# untitled2.net
KiCad netlist of a schematic drawn in EAGLE
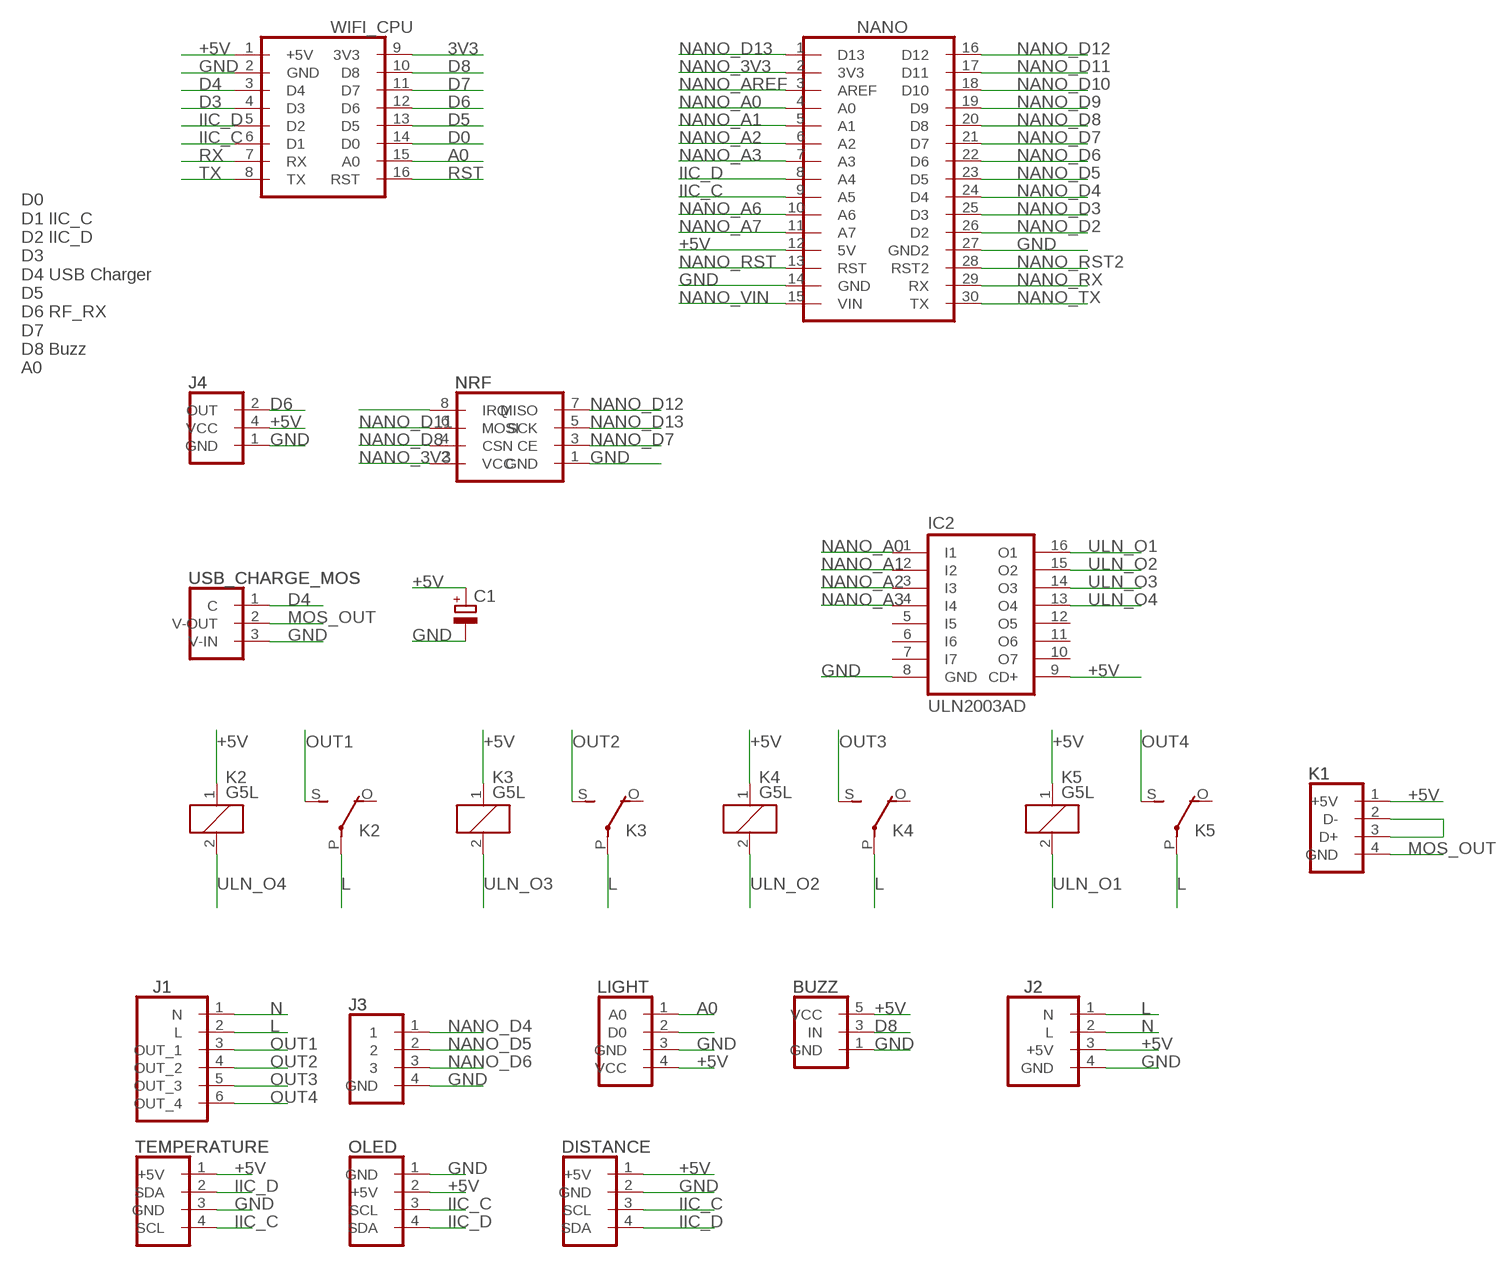
[diagram p0: schematic, sheet 1]

(export (version "E")
  (design (tool "Eeschema 10.0.6"))
  (components
    (comp (ref "BUZZ")
      (value "BUZZ_MODULE")
      (footprint "eagle-import:BUZZ_MODULE")
      (libsource (lib "eagle-import") (part "BUZZ_MODULE"))
    )
    (comp (ref "C1")
      (value "CPOL-EUE5-5")
      (footprint "eagle-import:E5-5")
      (libsource (lib "eagle-import") (part "CPOL-EUE5-5"))
    )
    (comp (ref "DISTANCE")
      (value "IIC_DISTANCE")
      (footprint "eagle-import:IIC_DISTANCE")
      (libsource (lib "eagle-import") (part "IIC_DISTANCE"))
    )
    (comp (ref "IC2")
      (value "ULN2003AD")
      (footprint "eagle-import:SO16")
      (libsource (lib "eagle-import") (part "ULN2003AD"))
    )
    (comp (ref "J1")
      (value "OUT_HEAD_6_AC_4CH")
      (footprint "eagle-import:OUT_HEAD_6_AC_4CH")
      (libsource (lib "eagle-import") (part "OUT_HEAD_6_AC_4CH"))
    )
    (comp (ref "J2")
      (value "AC_DCSIDE_2A")
      (footprint "eagle-import:AC_DC_SIDE_2A")
      (libsource (lib "eagle-import") (part "AC_DCSIDE_2A"))
    )
    (comp (ref "J3")
      (value "SELECT_1_IN_3")
      (footprint "eagle-import:SELECT_1_IN_3")
      (libsource (lib "eagle-import") (part "SELECT_1_IN_3"))
    )
    (comp (ref "J4")
      (value "315MHZ_RX_SMT_LONG")
      (footprint "eagle-import:315MHZ_RX_SMT_LONG")
      (libsource (lib "eagle-import") (part "315MHZ_RX_SMT_LONG"))
    )
    (comp (ref "K1")
      (value "USB_OUTUSB_V")
      (footprint "eagle-import:USB_V_OUT")
      (libsource (lib "eagle-import") (part "USB_OUTUSB_V"))
    )
    (comp (ref "K2")
      (value "G5L")
      (footprint "eagle-import:G5LE")
      (libsource (lib "eagle-import") (part "G5L"))
    )
    (comp (ref "K3")
      (value "G5L")
      (footprint "eagle-import:G5LE")
      (libsource (lib "eagle-import") (part "G5L"))
    )
    (comp (ref "K4")
      (value "G5L")
      (footprint "eagle-import:G5LE")
      (libsource (lib "eagle-import") (part "G5L"))
    )
    (comp (ref "K5")
      (value "G5L")
      (footprint "eagle-import:G5LE")
      (libsource (lib "eagle-import") (part "G5L"))
    )
    (comp (ref "LIGHT")
      (value "LIGHT_DEC")
      (footprint "eagle-import:LIGHT_DEC")
      (libsource (lib "eagle-import") (part "LIGHT_DEC"))
    )
    (comp (ref "NANO")
      (value "ARDUINO_NANO")
      (footprint "eagle-import:ARDUINO_NANO")
      (libsource (lib "eagle-import") (part "ARDUINO_NANO"))
    )
    (comp (ref "NRF")
      (value "NRF24L01_MODULE")
      (footprint "eagle-import:NRF24L01")
      (libsource (lib "eagle-import") (part "NRF24L01_MODULE"))
    )
    (comp (ref "OLED")
      (value "IIC_OLED")
      (footprint "eagle-import:IIC_OLED")
      (libsource (lib "eagle-import") (part "IIC_OLED"))
    )
    (comp (ref "TEMPERATURE")
      (value "IIC_TEMPERATURE")
      (footprint "eagle-import:IIC_TEMPERATURE")
      (libsource (lib "eagle-import") (part "IIC_TEMPERATURE"))
    )
    (comp (ref "USB_CHARGE_MOS")
      (value "MOS_IRF520")
      (footprint "eagle-import:MOS_IRF520")
      (libsource (lib "eagle-import") (part "MOS_IRF520"))
    )
    (comp (ref "WIFI_CPU")
      (value "ESP8266_MINI")
      (footprint "eagle-import:ESP8266_MINI")
      (libsource (lib "eagle-import") (part "ESP8266_MINI"))
    )
  )
  (nets
    (net (code "1") (name "/+5V") (class "Default")
      (node (ref "BUZZ") (pin "5") (pinfunction "VCC_5") (pintype "bidirectional"))
      (node (ref "C1") (pin "+") (pinfunction "+_+") (pintype "passive"))
      (node (ref "DISTANCE") (pin "1") (pinfunction "+5V_1") (pintype "bidirectional"))
      (node (ref "IC2") (pin "9") (pinfunction "CD+_9") (pintype "passive"))
      (node (ref "J2") (pin "3") (pinfunction "+5V_3") (pintype "bidirectional"))
      (node (ref "J4") (pin "4") (pinfunction "VCC_4") (pintype "bidirectional"))
      (node (ref "K1") (pin "1") (pinfunction "+5V_1") (pintype "bidirectional"))
      (node (ref "K2") (pin "1") (pinfunction "1_1") (pintype "passive"))
      (node (ref "K3") (pin "1") (pinfunction "1_1") (pintype "passive"))
      (node (ref "K4") (pin "1") (pinfunction "1_1") (pintype "passive"))
      (node (ref "K5") (pin "1") (pinfunction "1_1") (pintype "passive"))
      (node (ref "LIGHT") (pin "4") (pinfunction "VCC_4") (pintype "bidirectional"))
      (node (ref "NANO") (pin "12") (pinfunction "5V_12") (pintype "bidirectional"))
      (node (ref "OLED") (pin "2") (pinfunction "+5V_2") (pintype "bidirectional"))
      (node (ref "TEMPERATURE") (pin "1") (pinfunction "+5V_1") (pintype "bidirectional"))
      (node (ref "WIFI_CPU") (pin "1") (pinfunction "+5V_1") (pintype "bidirectional"))
    )
    (net (code "2") (name "/3V3") (class "Default")
      (node (ref "WIFI_CPU") (pin "9") (pinfunction "3V3_9") (pintype "bidirectional"))
    )
    (net (code "3") (name "/A0") (class "Default")
      (node (ref "LIGHT") (pin "1") (pinfunction "A0_1") (pintype "bidirectional"))
      (node (ref "WIFI_CPU") (pin "15") (pinfunction "A0_15") (pintype "bidirectional"))
    )
    (net (code "4") (name "/D0") (class "Default")
      (node (ref "WIFI_CPU") (pin "14") (pinfunction "D0_14") (pintype "bidirectional"))
    )
    (net (code "5") (name "/D3") (class "Default")
      (node (ref "WIFI_CPU") (pin "4") (pinfunction "D3_4") (pintype "bidirectional"))
    )
    (net (code "6") (name "/D4") (class "Default")
      (node (ref "USB_CHARGE_MOS") (pin "1") (pinfunction "C_1") (pintype "bidirectional"))
      (node (ref "WIFI_CPU") (pin "3") (pinfunction "D4_3") (pintype "bidirectional"))
    )
    (net (code "7") (name "/D5") (class "Default")
      (node (ref "WIFI_CPU") (pin "13") (pinfunction "D5_13") (pintype "bidirectional"))
    )
    (net (code "8") (name "/D6") (class "Default")
      (node (ref "J4") (pin "2") (pinfunction "OUT_2") (pintype "bidirectional"))
      (node (ref "WIFI_CPU") (pin "12") (pinfunction "D6_12") (pintype "bidirectional"))
    )
    (net (code "9") (name "/D7") (class "Default")
      (node (ref "WIFI_CPU") (pin "11") (pinfunction "D7_11") (pintype "bidirectional"))
    )
    (net (code "10") (name "/D8") (class "Default")
      (node (ref "BUZZ") (pin "3") (pinfunction "IN_3") (pintype "bidirectional"))
      (node (ref "WIFI_CPU") (pin "10") (pinfunction "D8_10") (pintype "bidirectional"))
    )
    (net (code "11") (name "/GND") (class "Default")
      (node (ref "BUZZ") (pin "1") (pinfunction "GND_1") (pintype "bidirectional"))
      (node (ref "C1") (pin "-") (pinfunction "-_-") (pintype "passive"))
      (node (ref "DISTANCE") (pin "2") (pinfunction "GND_2") (pintype "bidirectional"))
      (node (ref "IC2") (pin "8") (pinfunction "GND_8") (pintype "power_in"))
      (node (ref "J2") (pin "4") (pinfunction "GND_4") (pintype "bidirectional"))
      (node (ref "J3") (pin "4") (pinfunction "GND_4") (pintype "bidirectional"))
      (node (ref "J4") (pin "1") (pinfunction "GND_1") (pintype "bidirectional"))
      (node (ref "LIGHT") (pin "3") (pinfunction "GND_3") (pintype "bidirectional"))
      (node (ref "NANO") (pin "14") (pinfunction "GND_14") (pintype "bidirectional"))
      (node (ref "NANO") (pin "27") (pinfunction "GND2_27") (pintype "bidirectional"))
      (node (ref "NRF") (pin "1") (pinfunction "GND_1") (pintype "bidirectional"))
      (node (ref "OLED") (pin "1") (pinfunction "GND_1") (pintype "bidirectional"))
      (node (ref "TEMPERATURE") (pin "3") (pinfunction "GND_3") (pintype "bidirectional"))
      (node (ref "USB_CHARGE_MOS") (pin "3") (pinfunction "V-IN_3") (pintype "bidirectional"))
      (node (ref "WIFI_CPU") (pin "2") (pinfunction "GND_2") (pintype "bidirectional"))
    )
    (net (code "12") (name "/IIC_C") (class "Default")
      (node (ref "DISTANCE") (pin "3") (pinfunction "SCL_3") (pintype "bidirectional"))
      (node (ref "NANO") (pin "9") (pinfunction "A5_9") (pintype "bidirectional"))
      (node (ref "OLED") (pin "3") (pinfunction "SCL_3") (pintype "bidirectional"))
      (node (ref "TEMPERATURE") (pin "4") (pinfunction "SCL_4") (pintype "bidirectional"))
      (node (ref "WIFI_CPU") (pin "6") (pinfunction "D1_6") (pintype "bidirectional"))
    )
    (net (code "13") (name "/IIC_D") (class "Default")
      (node (ref "DISTANCE") (pin "4") (pinfunction "SDA_4") (pintype "bidirectional"))
      (node (ref "NANO") (pin "8") (pinfunction "A4_8") (pintype "bidirectional"))
      (node (ref "OLED") (pin "4") (pinfunction "SDA_4") (pintype "bidirectional"))
      (node (ref "TEMPERATURE") (pin "2") (pinfunction "SDA_2") (pintype "bidirectional"))
      (node (ref "WIFI_CPU") (pin "5") (pinfunction "D2_5") (pintype "bidirectional"))
    )
    (net (code "14") (name "/L") (class "Default")
      (node (ref "J1") (pin "2") (pinfunction "L_2") (pintype "bidirectional"))
      (node (ref "J2") (pin "1") (pinfunction "N_1") (pintype "bidirectional"))
      (node (ref "K2") (pin "P") (pinfunction "P_P") (pintype "passive"))
      (node (ref "K3") (pin "P") (pinfunction "P_P") (pintype "passive"))
      (node (ref "K4") (pin "P") (pinfunction "P_P") (pintype "passive"))
      (node (ref "K5") (pin "P") (pinfunction "P_P") (pintype "passive"))
    )
    (net (code "15") (name "/MOS_OUT") (class "Default")
      (node (ref "K1") (pin "4") (pinfunction "GND_4") (pintype "bidirectional"))
      (node (ref "USB_CHARGE_MOS") (pin "2") (pinfunction "V-OUT_2") (pintype "bidirectional"))
    )
    (net (code "16") (name "/N") (class "Default")
      (node (ref "J1") (pin "1") (pinfunction "N_1") (pintype "bidirectional"))
      (node (ref "J2") (pin "2") (pinfunction "L_2") (pintype "bidirectional"))
    )
    (net (code "17") (name "/NANO_3V3") (class "Default")
      (node (ref "NANO") (pin "2") (pinfunction "3V3_2") (pintype "bidirectional"))
      (node (ref "NRF") (pin "2") (pinfunction "VCC_2") (pintype "bidirectional"))
    )
    (net (code "18") (name "/NANO_A0") (class "Default")
      (node (ref "IC2") (pin "1") (pinfunction "I1_1") (pintype "input"))
      (node (ref "NANO") (pin "4") (pinfunction "A0_4") (pintype "bidirectional"))
    )
    (net (code "19") (name "/NANO_A1") (class "Default")
      (node (ref "IC2") (pin "2") (pinfunction "I2_2") (pintype "input"))
      (node (ref "NANO") (pin "5") (pinfunction "A1_5") (pintype "bidirectional"))
    )
    (net (code "20") (name "/NANO_A2") (class "Default")
      (node (ref "IC2") (pin "3") (pinfunction "I3_3") (pintype "input"))
      (node (ref "NANO") (pin "6") (pinfunction "A2_6") (pintype "bidirectional"))
    )
    (net (code "21") (name "/NANO_A3") (class "Default")
      (node (ref "IC2") (pin "4") (pinfunction "I4_4") (pintype "input"))
      (node (ref "NANO") (pin "7") (pinfunction "A3_7") (pintype "bidirectional"))
    )
    (net (code "22") (name "/NANO_A6") (class "Default")
      (node (ref "NANO") (pin "10") (pinfunction "A6_10") (pintype "bidirectional"))
    )
    (net (code "23") (name "/NANO_A7") (class "Default")
      (node (ref "NANO") (pin "11") (pinfunction "A7_11") (pintype "bidirectional"))
    )
    (net (code "24") (name "/NANO_AREF") (class "Default")
      (node (ref "NANO") (pin "3") (pinfunction "AREF_3") (pintype "bidirectional"))
    )
    (net (code "25") (name "/NANO_D2") (class "Default")
      (node (ref "NANO") (pin "26") (pinfunction "D2_26") (pintype "bidirectional"))
    )
    (net (code "26") (name "/NANO_D3") (class "Default")
      (node (ref "NANO") (pin "25") (pinfunction "D3_25") (pintype "bidirectional"))
    )
    (net (code "27") (name "/NANO_D4") (class "Default")
      (node (ref "J3") (pin "1") (pinfunction "1_1") (pintype "bidirectional"))
      (node (ref "NANO") (pin "24") (pinfunction "D4_24") (pintype "bidirectional"))
    )
    (net (code "28") (name "/NANO_D5") (class "Default")
      (node (ref "J3") (pin "2") (pinfunction "2_2") (pintype "bidirectional"))
      (node (ref "NANO") (pin "23") (pinfunction "D5_23") (pintype "bidirectional"))
    )
    (net (code "29") (name "/NANO_D6") (class "Default")
      (node (ref "J3") (pin "3") (pinfunction "3_3") (pintype "bidirectional"))
      (node (ref "NANO") (pin "22") (pinfunction "D6_22") (pintype "bidirectional"))
    )
    (net (code "30") (name "/NANO_D7") (class "Default")
      (node (ref "NANO") (pin "21") (pinfunction "D7_21") (pintype "bidirectional"))
      (node (ref "NRF") (pin "3") (pinfunction "CE_3") (pintype "bidirectional"))
    )
    (net (code "31") (name "/NANO_D8") (class "Default")
      (node (ref "NANO") (pin "20") (pinfunction "D8_20") (pintype "bidirectional"))
      (node (ref "NRF") (pin "4") (pinfunction "CSN_4") (pintype "bidirectional"))
    )
    (net (code "32") (name "/NANO_D9") (class "Default")
      (node (ref "NANO") (pin "19") (pinfunction "D9_19") (pintype "bidirectional"))
    )
    (net (code "33") (name "/NANO_D10") (class "Default")
      (node (ref "NANO") (pin "18") (pinfunction "D10_18") (pintype "bidirectional"))
    )
    (net (code "34") (name "/NANO_D11") (class "Default")
      (node (ref "NANO") (pin "17") (pinfunction "D11_17") (pintype "bidirectional"))
      (node (ref "NRF") (pin "6") (pinfunction "MOSI_6") (pintype "bidirectional"))
    )
    (net (code "35") (name "/NANO_D12") (class "Default")
      (node (ref "NANO") (pin "16") (pinfunction "D12_16") (pintype "bidirectional"))
      (node (ref "NRF") (pin "7") (pinfunction "MISO_7") (pintype "bidirectional"))
    )
    (net (code "36") (name "/NANO_D13") (class "Default")
      (node (ref "NANO") (pin "1") (pinfunction "D13_1") (pintype "bidirectional"))
      (node (ref "NRF") (pin "5") (pinfunction "SCK_5") (pintype "bidirectional"))
    )
    (net (code "37") (name "/NANO_RST") (class "Default")
      (node (ref "NANO") (pin "13") (pinfunction "RST_13") (pintype "bidirectional"))
    )
    (net (code "38") (name "/NANO_RST2") (class "Default")
      (node (ref "NANO") (pin "28") (pinfunction "RST2_28") (pintype "bidirectional"))
    )
    (net (code "39") (name "/NANO_RX") (class "Default")
      (node (ref "NANO") (pin "29") (pinfunction "RX_29") (pintype "bidirectional"))
    )
    (net (code "40") (name "/NANO_TX") (class "Default")
      (node (ref "NANO") (pin "30") (pinfunction "TX_30") (pintype "bidirectional"))
    )
    (net (code "41") (name "/NANO_VIN") (class "Default")
      (node (ref "NANO") (pin "15") (pinfunction "VIN_15") (pintype "bidirectional"))
    )
    (net (code "42") (name "/OUT1") (class "Default")
      (node (ref "J1") (pin "3") (pinfunction "OUT_1_3") (pintype "bidirectional"))
      (node (ref "K2") (pin "S") (pinfunction "S_S") (pintype "passive"))
    )
    (net (code "43") (name "/OUT2") (class "Default")
      (node (ref "J1") (pin "4") (pinfunction "OUT_2_4") (pintype "bidirectional"))
      (node (ref "K3") (pin "S") (pinfunction "S_S") (pintype "passive"))
    )
    (net (code "44") (name "/OUT3") (class "Default")
      (node (ref "J1") (pin "5") (pinfunction "OUT_3_5") (pintype "bidirectional"))
      (node (ref "K4") (pin "S") (pinfunction "S_S") (pintype "passive"))
    )
    (net (code "45") (name "/OUT4") (class "Default")
      (node (ref "J1") (pin "6") (pinfunction "OUT_4_6") (pintype "bidirectional"))
      (node (ref "K5") (pin "S") (pinfunction "S_S") (pintype "passive"))
    )
    (net (code "46") (name "/RST") (class "Default")
      (node (ref "WIFI_CPU") (pin "16") (pinfunction "RST_16") (pintype "bidirectional"))
    )
    (net (code "47") (name "/RX") (class "Default")
      (node (ref "WIFI_CPU") (pin "7") (pinfunction "RX_7") (pintype "bidirectional"))
    )
    (net (code "48") (name "/TX") (class "Default")
      (node (ref "WIFI_CPU") (pin "8") (pinfunction "TX_8") (pintype "bidirectional"))
    )
    (net (code "49") (name "/ULN_O1") (class "Default")
      (node (ref "IC2") (pin "16") (pinfunction "O1_16") (pintype "open_collector"))
      (node (ref "K5") (pin "2") (pinfunction "2_2") (pintype "passive"))
    )
    (net (code "50") (name "/ULN_O2") (class "Default")
      (node (ref "IC2") (pin "15") (pinfunction "O2_15") (pintype "open_collector"))
      (node (ref "K4") (pin "2") (pinfunction "2_2") (pintype "passive"))
    )
    (net (code "51") (name "/ULN_O3") (class "Default")
      (node (ref "IC2") (pin "14") (pinfunction "O3_14") (pintype "open_collector"))
      (node (ref "K3") (pin "2") (pinfunction "2_2") (pintype "passive"))
    )
    (net (code "52") (name "/ULN_O4") (class "Default")
      (node (ref "IC2") (pin "13") (pinfunction "O4_13") (pintype "open_collector"))
      (node (ref "K2") (pin "2") (pinfunction "2_2") (pintype "passive"))
    )
    (net (code "53") (name "Net-(K1-D+)") (class "Default")
      (node (ref "K1") (pin "2") (pinfunction "D-_2") (pintype "bidirectional"))
      (node (ref "K1") (pin "3") (pinfunction "D+_3") (pintype "bidirectional"))
    )
    (net (code "54") (name "unconnected-(IC2-I5-Pad5)") (class "Default")
      (node (ref "IC2") (pin "5") (pinfunction "I5_5") (pintype "input"))
    )
    (net (code "55") (name "unconnected-(IC2-I6-Pad6)") (class "Default")
      (node (ref "IC2") (pin "6") (pinfunction "I6_6") (pintype "input"))
    )
    (net (code "56") (name "unconnected-(IC2-I7-Pad7)") (class "Default")
      (node (ref "IC2") (pin "7") (pinfunction "I7_7") (pintype "input"))
    )
    (net (code "57") (name "unconnected-(IC2-O5-Pad12)") (class "Default")
      (node (ref "IC2") (pin "12") (pinfunction "O5_12") (pintype "open_collector"))
    )
    (net (code "58") (name "unconnected-(IC2-O6-Pad11)") (class "Default")
      (node (ref "IC2") (pin "11") (pinfunction "O6_11") (pintype "open_collector"))
    )
    (net (code "59") (name "unconnected-(IC2-O7-Pad10)") (class "Default")
      (node (ref "IC2") (pin "10") (pinfunction "O7_10") (pintype "open_collector"))
    )
    (net (code "60") (name "unconnected-(K2-PadO)") (class "Default")
      (node (ref "K2") (pin "O") (pinfunction "O_O") (pintype "passive"))
    )
    (net (code "61") (name "unconnected-(K3-PadO)") (class "Default")
      (node (ref "K3") (pin "O") (pinfunction "O_O") (pintype "passive"))
    )
    (net (code "62") (name "unconnected-(K4-PadO)") (class "Default")
      (node (ref "K4") (pin "O") (pinfunction "O_O") (pintype "passive"))
    )
    (net (code "63") (name "unconnected-(K5-PadO)") (class "Default")
      (node (ref "K5") (pin "O") (pinfunction "O_O") (pintype "passive"))
    )
    (net (code "64") (name "unconnected-(LIGHT-D0-Pad2)") (class "Default")
      (node (ref "LIGHT") (pin "2") (pinfunction "D0_2") (pintype "bidirectional"))
    )
    (net (code "65") (name "unconnected-(NRF-IRQ-Pad8)") (class "Default")
      (node (ref "NRF") (pin "8") (pinfunction "IRQ_8") (pintype "bidirectional"))
    )
  )
)
